# main.net
KiCad netlist of a schematic drawn in EAGLE
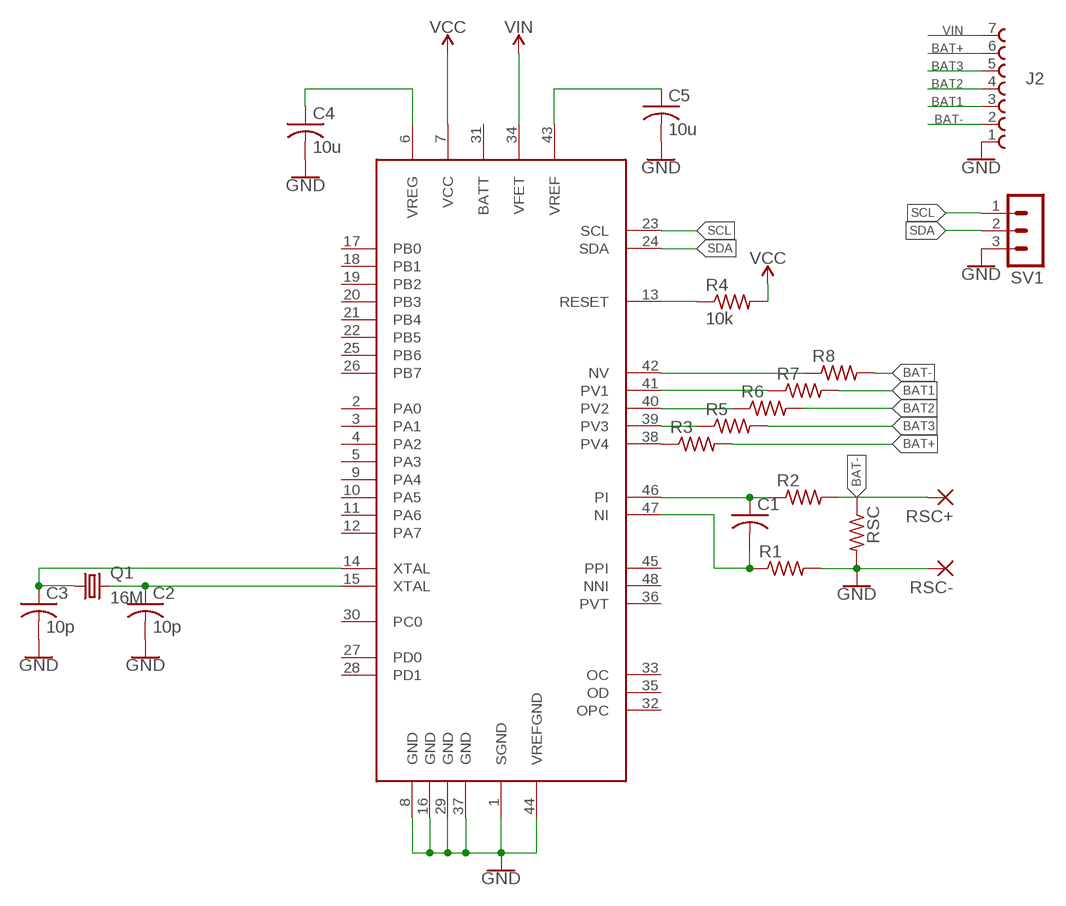
[diagram p0: schematic, sheet 1]

(export (version "E")
  (design (tool "Eeschema 10.0.6"))
  (components
    (comp (ref "C1")
      (value "C-USC0805")
      (footprint "eagle-import:C0805")
      (libsource (lib "eagle-import") (part "C-USC0805"))
    )
    (comp (ref "C2")
      (value "10p")
      (footprint "eagle-import:C0805")
      (libsource (lib "eagle-import") (part "C-USC0805"))
    )
    (comp (ref "C3")
      (value "10p")
      (footprint "eagle-import:C0805")
      (libsource (lib "eagle-import") (part "C-USC0805"))
    )
    (comp (ref "C4")
      (value "10u")
      (footprint "eagle-import:C0805")
      (libsource (lib "eagle-import") (part "C-USC0805"))
    )
    (comp (ref "C5")
      (value "10u")
      (footprint "eagle-import:C0805")
      (libsource (lib "eagle-import") (part "C-USC0805"))
    )
    (comp (ref "J2")
      (value "691136710007")
      (footprint "eagle-import:691136710007")
      (libsource (lib "eagle-import") (part "691136710007"))
    )
    (comp (ref "Q1")
      (value "16M")
      (footprint "eagle-import:HC49U-V")
      (libsource (lib "eagle-import") (part "CRYSTALHC49U-V"))
    )
    (comp (ref "R1")
      (value "R-US_R0805")
      (footprint "eagle-import:R0805")
      (libsource (lib "eagle-import") (part "R-US_R0805"))
    )
    (comp (ref "R2")
      (value "R-US_R0805")
      (footprint "eagle-import:R0805")
      (libsource (lib "eagle-import") (part "R-US_R0805"))
    )
    (comp (ref "R3")
      (value "R-US_R0805")
      (footprint "eagle-import:R0805")
      (libsource (lib "eagle-import") (part "R-US_R0805"))
    )
    (comp (ref "R4")
      (value "10k")
      (footprint "eagle-import:R0603")
      (libsource (lib "eagle-import") (part "R-US_R0603"))
    )
    (comp (ref "R5")
      (value "R-US_R0805")
      (footprint "eagle-import:R0805")
      (libsource (lib "eagle-import") (part "R-US_R0805"))
    )
    (comp (ref "R6")
      (value "R-US_R0805")
      (footprint "eagle-import:R0805")
      (libsource (lib "eagle-import") (part "R-US_R0805"))
    )
    (comp (ref "R7")
      (value "R-US_R0805")
      (footprint "eagle-import:R0805")
      (libsource (lib "eagle-import") (part "R-US_R0805"))
    )
    (comp (ref "R8")
      (value "R-US_R0805")
      (footprint "eagle-import:R0805")
      (libsource (lib "eagle-import") (part "R-US_R0805"))
    )
    (comp (ref "RSC")
      (value "R-US_R0805")
      (footprint "eagle-import:R0805")
      (libsource (lib "eagle-import") (part "R-US_R0805"))
    )
    (comp (ref "RSC+")
      (value "2,54/1,0")
      (footprint "eagle-import:2,54_1,0")
      (libsource (lib "eagle-import") (part "2,54/1,0"))
    )
    (comp (ref "RSC-")
      (value "2,54/1,0")
      (footprint "eagle-import:2,54_1,0")
      (libsource (lib "eagle-import") (part "2,54/1,0"))
    )
    (comp (ref "SV1")
      (value "MA03-1")
      (footprint "eagle-import:MA03-1")
      (libsource (lib "eagle-import") (part "MA03-1"))
    )
    (comp (ref "U$1")
      (value "ATMEGA406")
      (footprint "eagle-import:LQFP48")
      (libsource (lib "eagle-import") (part "ATMEGA406"))
    )
  )
  (nets
    (net (code "1") (name "BAT+") (class "Default")
      (node (ref "J2") (pin "6") (pinfunction "6_6") (pintype "passive"))
      (node (ref "R3") (pin "2") (pinfunction "2_2") (pintype "passive"))
    )
    (net (code "2") (name "BAT-") (class "Default")
      (node (ref "J2") (pin "2") (pinfunction "2_2") (pintype "passive"))
      (node (ref "R2") (pin "2") (pinfunction "2_2") (pintype "passive"))
      (node (ref "R8") (pin "2") (pinfunction "2_2") (pintype "passive"))
      (node (ref "RSC") (pin "1") (pinfunction "1_1") (pintype "passive"))
      (node (ref "RSC+") (pin "1") (pinfunction "P_1") (pintype "passive"))
    )
    (net (code "3") (name "BAT1") (class "Default")
      (node (ref "J2") (pin "3") (pinfunction "3_3") (pintype "passive"))
      (node (ref "R7") (pin "2") (pinfunction "2_2") (pintype "passive"))
    )
    (net (code "4") (name "BAT2") (class "Default")
      (node (ref "J2") (pin "4") (pinfunction "4_4") (pintype "passive"))
      (node (ref "R6") (pin "2") (pinfunction "2_2") (pintype "passive"))
    )
    (net (code "5") (name "BAT3") (class "Default")
      (node (ref "J2") (pin "5") (pinfunction "5_5") (pintype "passive"))
      (node (ref "R5") (pin "2") (pinfunction "2_2") (pintype "passive"))
    )
    (net (code "6") (name "GND") (class "Default")
      (node (ref "C2") (pin "2") (pinfunction "2_2") (pintype "passive"))
      (node (ref "C3") (pin "2") (pinfunction "2_2") (pintype "passive"))
      (node (ref "C4") (pin "2") (pinfunction "2_2") (pintype "passive"))
      (node (ref "C5") (pin "2") (pinfunction "2_2") (pintype "passive"))
      (node (ref "J2") (pin "1") (pinfunction "1_1") (pintype "passive"))
      (node (ref "R1") (pin "2") (pinfunction "2_2") (pintype "passive"))
      (node (ref "RSC") (pin "2") (pinfunction "2_2") (pintype "passive"))
      (node (ref "RSC-") (pin "1") (pinfunction "P_1") (pintype "passive"))
      (node (ref "SV1") (pin "3") (pinfunction "3_3") (pintype "passive"))
      (node (ref "U$1") (pin "1") (pinfunction "SGND_1") (pintype "bidirectional"))
      (node (ref "U$1") (pin "16") (pinfunction "GND_16") (pintype "bidirectional"))
      (node (ref "U$1") (pin "29") (pinfunction "GND_29") (pintype "bidirectional"))
      (node (ref "U$1") (pin "37") (pinfunction "GND_37") (pintype "bidirectional"))
      (node (ref "U$1") (pin "44") (pinfunction "VREFGND_44") (pintype "bidirectional"))
      (node (ref "U$1") (pin "8") (pinfunction "GND_8") (pintype "bidirectional"))
    )
    (net (code "7") (name "Net-(C2-Pad1)") (class "Default")
      (node (ref "C2") (pin "1") (pinfunction "1_1") (pintype "passive"))
      (node (ref "Q1") (pin "2") (pinfunction "2_2") (pintype "passive"))
      (node (ref "U$1") (pin "15") (pinfunction "XTAL_15") (pintype "bidirectional"))
    )
    (net (code "8") (name "Net-(C3-Pad1)") (class "Default")
      (node (ref "C3") (pin "1") (pinfunction "1_1") (pintype "passive"))
      (node (ref "Q1") (pin "1") (pinfunction "1_1") (pintype "passive"))
      (node (ref "U$1") (pin "14") (pinfunction "XTAL_14") (pintype "bidirectional"))
    )
    (net (code "9") (name "Net-(U$1-NI)") (class "Default")
      (node (ref "C1") (pin "2") (pinfunction "2_2") (pintype "passive"))
      (node (ref "R1") (pin "1") (pinfunction "1_1") (pintype "passive"))
      (node (ref "U$1") (pin "47") (pinfunction "NI_47") (pintype "bidirectional"))
    )
    (net (code "10") (name "Net-(U$1-NV)") (class "Default")
      (node (ref "R8") (pin "1") (pinfunction "1_1") (pintype "passive"))
      (node (ref "U$1") (pin "42") (pinfunction "NV_42") (pintype "bidirectional"))
    )
    (net (code "11") (name "Net-(U$1-PI)") (class "Default")
      (node (ref "C1") (pin "1") (pinfunction "1_1") (pintype "passive"))
      (node (ref "R2") (pin "1") (pinfunction "1_1") (pintype "passive"))
      (node (ref "U$1") (pin "46") (pinfunction "PI_46") (pintype "bidirectional"))
    )
    (net (code "12") (name "Net-(U$1-PV1)") (class "Default")
      (node (ref "R7") (pin "1") (pinfunction "1_1") (pintype "passive"))
      (node (ref "U$1") (pin "41") (pinfunction "PV1_41") (pintype "bidirectional"))
    )
    (net (code "13") (name "Net-(U$1-PV2)") (class "Default")
      (node (ref "R6") (pin "1") (pinfunction "1_1") (pintype "passive"))
      (node (ref "U$1") (pin "40") (pinfunction "PV2_40") (pintype "bidirectional"))
    )
    (net (code "14") (name "Net-(U$1-PV3)") (class "Default")
      (node (ref "R5") (pin "1") (pinfunction "1_1") (pintype "passive"))
      (node (ref "U$1") (pin "39") (pinfunction "PV3_39") (pintype "bidirectional"))
    )
    (net (code "15") (name "Net-(U$1-PV4)") (class "Default")
      (node (ref "R3") (pin "1") (pinfunction "1_1") (pintype "passive"))
      (node (ref "U$1") (pin "38") (pinfunction "PV4_38") (pintype "bidirectional"))
    )
    (net (code "16") (name "Net-(U$1-RESET)") (class "Default")
      (node (ref "R4") (pin "1") (pinfunction "1_1") (pintype "passive"))
      (node (ref "U$1") (pin "13") (pinfunction "RESET_13") (pintype "bidirectional"))
    )
    (net (code "17") (name "Net-(U$1-VREF)") (class "Default")
      (node (ref "C5") (pin "1") (pinfunction "1_1") (pintype "passive"))
      (node (ref "U$1") (pin "43") (pinfunction "VREF_43") (pintype "bidirectional"))
    )
    (net (code "18") (name "Net-(U$1-VREG)") (class "Default")
      (node (ref "C4") (pin "1") (pinfunction "1_1") (pintype "passive"))
      (node (ref "U$1") (pin "6") (pinfunction "VREG_6") (pintype "bidirectional"))
    )
    (net (code "19") (name "SCL") (class "Default")
      (node (ref "SV1") (pin "1") (pinfunction "1_1") (pintype "passive"))
      (node (ref "U$1") (pin "23") (pinfunction "SCL_23") (pintype "bidirectional"))
    )
    (net (code "20") (name "SDA") (class "Default")
      (node (ref "SV1") (pin "2") (pinfunction "2_2") (pintype "passive"))
      (node (ref "U$1") (pin "24") (pinfunction "SDA_24") (pintype "bidirectional"))
    )
    (net (code "21") (name "VCC") (class "Default")
      (node (ref "R4") (pin "2") (pinfunction "2_2") (pintype "passive"))
      (node (ref "U$1") (pin "7") (pinfunction "VCC_7") (pintype "bidirectional"))
    )
    (net (code "22") (name "VIN") (class "Default")
      (node (ref "J2") (pin "7") (pinfunction "7_7") (pintype "passive"))
      (node (ref "U$1") (pin "34") (pinfunction "VFET_34") (pintype "bidirectional"))
    )
    (net (code "23") (name "unconnected-(U$1-BATT-Pad31)") (class "Default")
      (node (ref "U$1") (pin "31") (pinfunction "BATT_31") (pintype "bidirectional"))
    )
    (net (code "24") (name "unconnected-(U$1-NNI-Pad48)") (class "Default")
      (node (ref "U$1") (pin "48") (pinfunction "NNI_48") (pintype "bidirectional"))
    )
    (net (code "25") (name "unconnected-(U$1-OC-Pad33)") (class "Default")
      (node (ref "U$1") (pin "33") (pinfunction "OC_33") (pintype "bidirectional"))
    )
    (net (code "26") (name "unconnected-(U$1-OD-Pad35)") (class "Default")
      (node (ref "U$1") (pin "35") (pinfunction "OD_35") (pintype "bidirectional"))
    )
    (net (code "27") (name "unconnected-(U$1-OPC-Pad32)") (class "Default")
      (node (ref "U$1") (pin "32") (pinfunction "OPC_32") (pintype "bidirectional"))
    )
    (net (code "28") (name "unconnected-(U$1-PA0-Pad2)") (class "Default")
      (node (ref "U$1") (pin "2") (pinfunction "PA0_2") (pintype "bidirectional"))
    )
    (net (code "29") (name "unconnected-(U$1-PA1-Pad3)") (class "Default")
      (node (ref "U$1") (pin "3") (pinfunction "PA1_3") (pintype "bidirectional"))
    )
    (net (code "30") (name "unconnected-(U$1-PA2-Pad4)") (class "Default")
      (node (ref "U$1") (pin "4") (pinfunction "PA2_4") (pintype "bidirectional"))
    )
    (net (code "31") (name "unconnected-(U$1-PA3-Pad5)") (class "Default")
      (node (ref "U$1") (pin "5") (pinfunction "PA3_5") (pintype "bidirectional"))
    )
    (net (code "32") (name "unconnected-(U$1-PA4-Pad9)") (class "Default")
      (node (ref "U$1") (pin "9") (pinfunction "PA4_9") (pintype "bidirectional"))
    )
    (net (code "33") (name "unconnected-(U$1-PA5-Pad10)") (class "Default")
      (node (ref "U$1") (pin "10") (pinfunction "PA5_10") (pintype "bidirectional"))
    )
    (net (code "34") (name "unconnected-(U$1-PA6-Pad11)") (class "Default")
      (node (ref "U$1") (pin "11") (pinfunction "PA6_11") (pintype "bidirectional"))
    )
    (net (code "35") (name "unconnected-(U$1-PA7-Pad12)") (class "Default")
      (node (ref "U$1") (pin "12") (pinfunction "PA7_12") (pintype "bidirectional"))
    )
    (net (code "36") (name "unconnected-(U$1-PB0-Pad17)") (class "Default")
      (node (ref "U$1") (pin "17") (pinfunction "PB0_17") (pintype "bidirectional"))
    )
    (net (code "37") (name "unconnected-(U$1-PB1-Pad18)") (class "Default")
      (node (ref "U$1") (pin "18") (pinfunction "PB1_18") (pintype "bidirectional"))
    )
    (net (code "38") (name "unconnected-(U$1-PB2-Pad19)") (class "Default")
      (node (ref "U$1") (pin "19") (pinfunction "PB2_19") (pintype "bidirectional"))
    )
    (net (code "39") (name "unconnected-(U$1-PB3-Pad20)") (class "Default")
      (node (ref "U$1") (pin "20") (pinfunction "PB3_20") (pintype "bidirectional"))
    )
    (net (code "40") (name "unconnected-(U$1-PB4-Pad21)") (class "Default")
      (node (ref "U$1") (pin "21") (pinfunction "PB4_21") (pintype "bidirectional"))
    )
    (net (code "41") (name "unconnected-(U$1-PB5-Pad22)") (class "Default")
      (node (ref "U$1") (pin "22") (pinfunction "PB5_22") (pintype "bidirectional"))
    )
    (net (code "42") (name "unconnected-(U$1-PB6-Pad25)") (class "Default")
      (node (ref "U$1") (pin "25") (pinfunction "PB6_25") (pintype "bidirectional"))
    )
    (net (code "43") (name "unconnected-(U$1-PB7-Pad26)") (class "Default")
      (node (ref "U$1") (pin "26") (pinfunction "PB7_26") (pintype "bidirectional"))
    )
    (net (code "44") (name "unconnected-(U$1-PC0-Pad30)") (class "Default")
      (node (ref "U$1") (pin "30") (pinfunction "PC0_30") (pintype "bidirectional"))
    )
    (net (code "45") (name "unconnected-(U$1-PD0-Pad27)") (class "Default")
      (node (ref "U$1") (pin "27") (pinfunction "PD0_27") (pintype "bidirectional"))
    )
    (net (code "46") (name "unconnected-(U$1-PD1-Pad28)") (class "Default")
      (node (ref "U$1") (pin "28") (pinfunction "PD1_28") (pintype "bidirectional"))
    )
    (net (code "47") (name "unconnected-(U$1-PPI-Pad45)") (class "Default")
      (node (ref "U$1") (pin "45") (pinfunction "PPI_45") (pintype "bidirectional"))
    )
    (net (code "48") (name "unconnected-(U$1-PVT-Pad36)") (class "Default")
      (node (ref "U$1") (pin "36") (pinfunction "PVT_36") (pintype "bidirectional"))
    )
  )
)
